# MC3202.net
KiCad netlist of a schematic drawn in Altium Designer
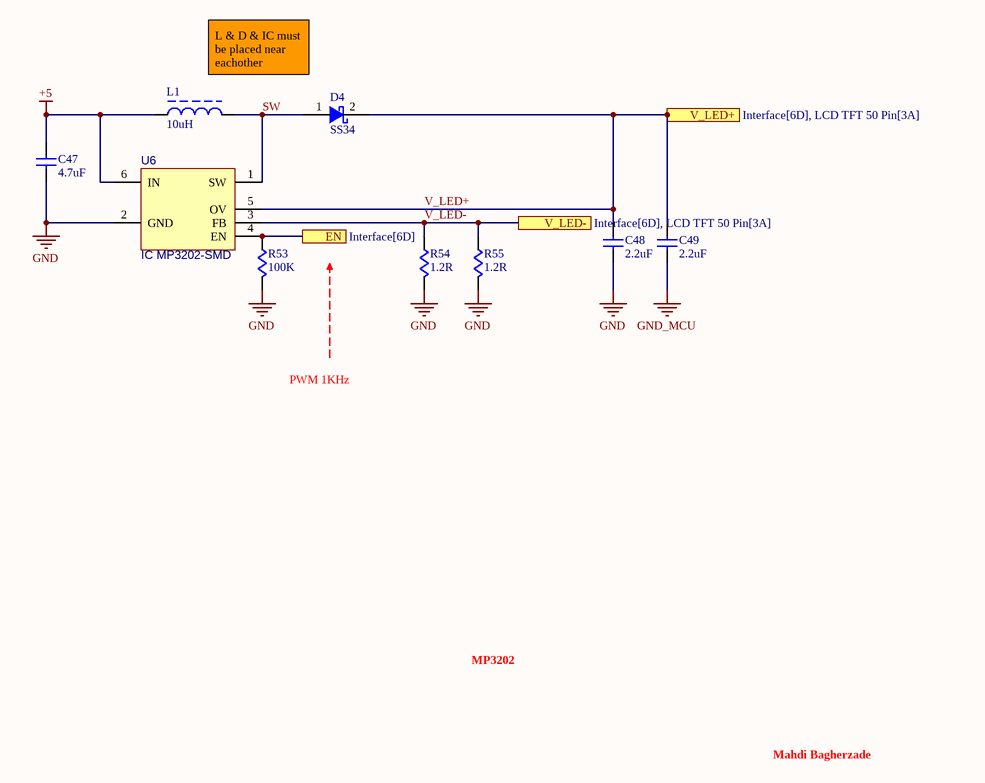
[diagram p0: MC3202.SchDoc]

(export (version "E")
  (design (tool "Eeschema 10.0.6"))
  (components
    (comp (ref "C47")
      (value "4.7uF")
      (footprint "C-0805")
      (description "CAPACITOR")
      (fields
        (field (name "VOLTAGE") "16V")
        (field (name "TOLERANCE") "X7R")
        (field (name "PUBLISHER") "Mahdi Bagherzadeh")
      )
      (libsource (lib "Mahdi-Bagherzadeh") (part "CAP-CER"))
    )
    (comp (ref "C48")
      (value "2.2uF")
      (footprint "C-0805")
      (description "CAPACITOR")
      (fields
        (field (name "VOLTAGE") "25V")
        (field (name "TOLERANCE") "X7R")
        (field (name "PUBLISHER") "Mahdi Bagherzadeh")
      )
      (libsource (lib "Mahdi-Bagherzadeh") (part "CAP-CER"))
    )
    (comp (ref "C49")
      (value "2.2uF")
      (footprint "C-0805")
      (description "CAPACITOR")
      (fields
        (field (name "VOLTAGE") "25V")
        (field (name "TOLERANCE") "X7R")
        (field (name "PUBLISHER") "Mahdi Bagherzadeh")
      )
      (libsource (lib "Mahdi-Bagherzadeh") (part "CAP-CER"))
    )
    (comp (ref "D4")
      (value "Diode Schottky SS34-SMD")
      (footprint "D-DO214AB")
      (description "DIODE")
      (fields (field (name "CODE") "SS34") (field (name "PUBLISHER") "Mahdi Bagherzadeh"))
      (libsource (lib "Mahdi-Bagherzadeh") (part "DIODE-SCHOTTKY"))
    )
    (comp (ref "L1")
      (value "10uH")
      (footprint "IND-SMD-1010")
      (description "INDUCATOR")
      (fields (field (name "Comment") "IND 10uH-10x10mm-SMD") (field (name "PUBLISHER") "Mahdi Bagherzadeh"))
      (libsource (lib "Mahdi-Bagherzadeh") (part "INDUCATOR"))
    )
    (comp (ref "R53")
      (value "100K")
      (footprint "R-0805")
      (description "RESISTOR")
      (fields
        (field (name "TOLERANCE") "5%")
        (field (name "POWER") "1/8W")
        (field (name "PUBLISHER") "Mahdi Bagherzadeh")
      )
      (libsource (lib "Mahdi-Bagherzadeh") (part "RES"))
    )
    (comp (ref "R54")
      (value "1.2R")
      (footprint "R-1206")
      (description "RESISTOR")
      (fields
        (field (name "TOLERANCE") "5%")
        (field (name "POWER") "1/8W")
        (field (name "PUBLISHER") "Mahdi Bagherzadeh")
      )
      (libsource (lib "Mahdi-Bagherzadeh") (part "RES"))
    )
    (comp (ref "R55")
      (value "1.2R")
      (footprint "R-1206")
      (description "RESISTOR")
      (fields
        (field (name "TOLERANCE") "5%")
        (field (name "POWER") "1/8W")
        (field (name "PUBLISHER") "Mahdi Bagherzadeh")
      )
      (libsource (lib "Mahdi-Bagherzadeh") (part "RES"))
    )
    (comp (ref "U6")
      (value "IC MP3202-SMD")
      (footprint "SOT23-6N")
      (description "IC")
      (fields (field (name "PUBLISHER") "Mahdi Bagherzadeh"))
      (libsource (lib "Mahdi-Bagherzadeh") (part "MP3202"))
    )
  )
  (nets
    (net (code "1") (name "+5") (class "Default")
      (node (ref "C47") (pin "1") (pinfunction "1_1") (pintype "passive"))
      (node (ref "L1") (pin "1") (pinfunction "1_1") (pintype "passive"))
      (node (ref "U6") (pin "6") (pinfunction "IN_6") (pintype "passive"))
    )
    (net (code "2") (name "/EN") (class "Default")
      (node (ref "R53") (pin "1") (pinfunction "1_1") (pintype "passive"))
      (node (ref "U6") (pin "4") (pinfunction "EN_4") (pintype "passive"))
    )
    (net (code "3") (name "/SW") (class "Default")
      (node (ref "D4") (pin "1") (pinfunction "A_1") (pintype "passive"))
      (node (ref "L1") (pin "2") (pinfunction "2_2") (pintype "passive"))
      (node (ref "U6") (pin "1") (pinfunction "SW_1") (pintype "power_in"))
    )
    (net (code "4") (name "/V_LED+") (class "Default")
      (node (ref "C48") (pin "1") (pinfunction "1_1") (pintype "passive"))
      (node (ref "C49") (pin "1") (pinfunction "1_1") (pintype "passive"))
      (node (ref "D4") (pin "2") (pinfunction "C_2") (pintype "passive"))
      (node (ref "U6") (pin "5") (pinfunction "OV_5") (pintype "passive"))
    )
    (net (code "5") (name "/V_LED-") (class "Default")
      (node (ref "R54") (pin "1") (pinfunction "1_1") (pintype "passive"))
      (node (ref "R55") (pin "1") (pinfunction "1_1") (pintype "passive"))
      (node (ref "U6") (pin "3") (pinfunction "FB_3") (pintype "passive"))
    )
    (net (code "6") (name "GND") (class "Default")
      (node (ref "C47") (pin "2") (pinfunction "2_2") (pintype "passive"))
      (node (ref "C48") (pin "2") (pinfunction "2_2") (pintype "passive"))
      (node (ref "R53") (pin "2") (pinfunction "2_2") (pintype "passive"))
      (node (ref "R54") (pin "2") (pinfunction "2_2") (pintype "passive"))
      (node (ref "R55") (pin "2") (pinfunction "2_2") (pintype "passive"))
      (node (ref "U6") (pin "2") (pinfunction "GND_2") (pintype "power_in"))
    )
    (net (code "7") (name "GND_MCU") (class "Default")
      (node (ref "C49") (pin "2") (pinfunction "2_2") (pintype "passive"))
    )
  )
)
